# LEDPowerTest.net
KiCad netlist of a schematic drawn in EAGLE
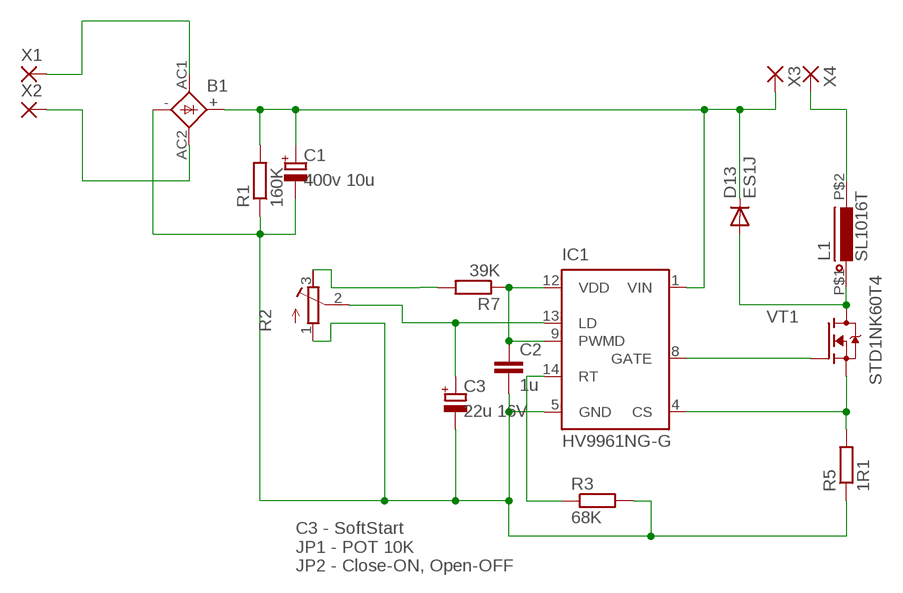
[diagram p0: schematic, sheet 1]

(export (version "E")
  (design (tool "Eeschema 10.0.6"))
  (components
    (comp (ref "B1")
      (value "BRIDGEDBS")
      (footprint "eagle-import:DBS")
      (libsource (lib "eagle-import") (part "BRIDGEDBS"))
    )
    (comp (ref "C1")
      (value "400v 10u")
      (footprint "eagle-import:E3,5-8")
      (libsource (lib "eagle-import") (part "CAP-POL_E3.5-8"))
    )
    (comp (ref "C2")
      (value "1u")
      (footprint "eagle-import:CAP0805")
      (libsource (lib "eagle-import") (part "CAP_0805"))
    )
    (comp (ref "C3")
      (value "22u 16V")
      (footprint "eagle-import:CT3528")
      (libsource (lib "eagle-import") (part "CAP-POL_3528"))
    )
    (comp (ref "D13")
      (value "ES1J")
      (footprint "eagle-import:DO214AC")
      (libsource (lib "eagle-import") (part "DIODE_ES1J"))
    )
    (comp (ref "IC1")
      (value "HV9961NG-G")
      (footprint "eagle-import:SOIC-16NG")
      (libsource (lib "eagle-import") (part "HV9910BNG"))
    )
    (comp (ref "L1")
      (value "SL1016T")
      (footprint "eagle-import:SL1016")
      (libsource (lib "eagle-import") (part "INDUCTORSL1016"))
    )
    (comp (ref "R1")
      (value "160K")
      (footprint "eagle-import:MF-0125")
      (libsource (lib "eagle-import") (part "R_MF-0125"))
    )
    (comp (ref "R2")
      (value "R_POT3296X")
      (footprint "eagle-import:POT-3296X")
      (libsource (lib "eagle-import") (part "R_POT3296X"))
    )
    (comp (ref "R3")
      (value "68K")
      (footprint "eagle-import:RESC2012X50")
      (libsource (lib "eagle-import") (part "R_R0805"))
    )
    (comp (ref "R5")
      (value "1R1")
      (footprint "eagle-import:MF-05")
      (libsource (lib "eagle-import") (part "R_MF-05"))
    )
    (comp (ref "R7")
      (value "39K")
      (footprint "eagle-import:RESC2012X50")
      (libsource (lib "eagle-import") (part "R_R0805"))
    )
    (comp (ref "VT1")
      (value "STD1NK60T4")
      (footprint "eagle-import:DPAK")
      (libsource (lib "eagle-import") (part "FET-NDPAK"))
    )
    (comp (ref "X1")
      (value "WIREPAD-SMD2")
      (footprint "eagle-import:PAD-1.27X2.54")
      (libsource (lib "eagle-import") (part "WIREPAD-SMD2"))
    )
    (comp (ref "X2")
      (value "WIREPAD-SMD2")
      (footprint "eagle-import:PAD-1.27X2.54")
      (libsource (lib "eagle-import") (part "WIREPAD-SMD2"))
    )
    (comp (ref "X3")
      (value "WIREPAD-SMD2")
      (footprint "eagle-import:PAD-1.27X2.54")
      (libsource (lib "eagle-import") (part "WIREPAD-SMD2"))
    )
    (comp (ref "X4")
      (value "WIREPAD-SMD2")
      (footprint "eagle-import:PAD-1.27X2.54")
      (libsource (lib "eagle-import") (part "WIREPAD-SMD2"))
    )
  )
  (nets
    (net (code "1") (name "Net-(IC1-CS)") (class "Default")
      (node (ref "IC1") (pin "4") (pinfunction "CS_4") (pintype "input"))
      (node (ref "R5") (pin "2") (pinfunction "2_2") (pintype "passive"))
      (node (ref "VT1") (pin "S") (pinfunction "S_S") (pintype "passive"))
    )
    (net (code "2") (name "Net-(IC1-GATE)") (class "Default")
      (node (ref "IC1") (pin "8") (pinfunction "GATE_8") (pintype "output"))
      (node (ref "VT1") (pin "G") (pinfunction "G_G") (pintype "passive"))
    )
    (net (code "3") (name "Net-(IC1-GND)") (class "Default")
      (node (ref "B1") (pin "-") (pinfunction "-_-") (pintype "passive"))
      (node (ref "C1") (pin "-") (pinfunction "-_-") (pintype "passive"))
      (node (ref "C2") (pin "2") (pinfunction "2_2") (pintype "passive"))
      (node (ref "C3") (pin "-") (pinfunction "-_-") (pintype "passive"))
      (node (ref "IC1") (pin "5") (pinfunction "GND_5") (pintype "power_in"))
      (node (ref "R1") (pin "1") (pinfunction "1_1") (pintype "passive"))
      (node (ref "R2") (pin "1") (pinfunction "A_1") (pintype "passive"))
      (node (ref "R3") (pin "2") (pinfunction "2_2") (pintype "passive"))
      (node (ref "R5") (pin "1") (pinfunction "1_1") (pintype "passive"))
    )
    (net (code "4") (name "Net-(IC1-LD)") (class "Default")
      (node (ref "C3") (pin "+") (pinfunction "+_+") (pintype "passive"))
      (node (ref "IC1") (pin "13") (pinfunction "LD_13") (pintype "input"))
      (node (ref "R2") (pin "2") (pinfunction "S_2") (pintype "passive"))
    )
    (net (code "5") (name "Net-(IC1-PWMD)") (class "Default")
      (node (ref "C2") (pin "1") (pinfunction "1_1") (pintype "passive"))
      (node (ref "IC1") (pin "12") (pinfunction "VDD_12") (pintype "power_in"))
      (node (ref "IC1") (pin "9") (pinfunction "PWMD_9") (pintype "input"))
      (node (ref "R7") (pin "1") (pinfunction "1_1") (pintype "passive"))
    )
    (net (code "6") (name "Net-(IC1-RT)") (class "Default")
      (node (ref "IC1") (pin "14") (pinfunction "RT_14") (pintype "passive"))
      (node (ref "R3") (pin "1") (pinfunction "1_1") (pintype "passive"))
    )
    (net (code "7") (name "Net-(IC1-VIN)") (class "Default")
      (node (ref "B1") (pin "+") (pinfunction "+_+") (pintype "passive"))
      (node (ref "C1") (pin "+") (pinfunction "+_+") (pintype "passive"))
      (node (ref "D13") (pin "C") (pinfunction "C_C") (pintype "passive"))
      (node (ref "IC1") (pin "1") (pinfunction "VIN_1") (pintype "input"))
      (node (ref "R1") (pin "2") (pinfunction "2_2") (pintype "passive"))
      (node (ref "X3") (pin "P$1") (pinfunction "P_P$1") (pintype "passive"))
    )
    (net (code "8") (name "Net-(L1-1)") (class "Default")
      (node (ref "D13") (pin "A") (pinfunction "A_A") (pintype "passive"))
      (node (ref "L1") (pin "P$1") (pinfunction "1_P$1") (pintype "passive"))
      (node (ref "VT1") (pin "D") (pinfunction "D_D") (pintype "passive"))
    )
    (net (code "9") (name "Net-(L1-2)") (class "Default")
      (node (ref "L1") (pin "P$2") (pinfunction "2_P$2") (pintype "passive"))
      (node (ref "X4") (pin "P$1") (pinfunction "P_P$1") (pintype "passive"))
    )
    (net (code "10") (name "Net-(R2-E)") (class "Default")
      (node (ref "R2") (pin "3") (pinfunction "E_3") (pintype "passive"))
      (node (ref "R7") (pin "2") (pinfunction "2_2") (pintype "passive"))
    )
    (net (code "11") (name "Net-(X1-P)") (class "Default")
      (node (ref "B1") (pin "AC1") (pinfunction "AC1_AC1") (pintype "passive"))
      (node (ref "X1") (pin "P$1") (pinfunction "P_P$1") (pintype "passive"))
    )
    (net (code "12") (name "Net-(X2-P)") (class "Default")
      (node (ref "B1") (pin "AC2") (pinfunction "AC2_AC2") (pintype "passive"))
      (node (ref "X2") (pin "P$1") (pinfunction "P_P$1") (pintype "passive"))
    )
  )
)
